# schematic-oshtest.net
KiCad netlist of a schematic drawn in EAGLE
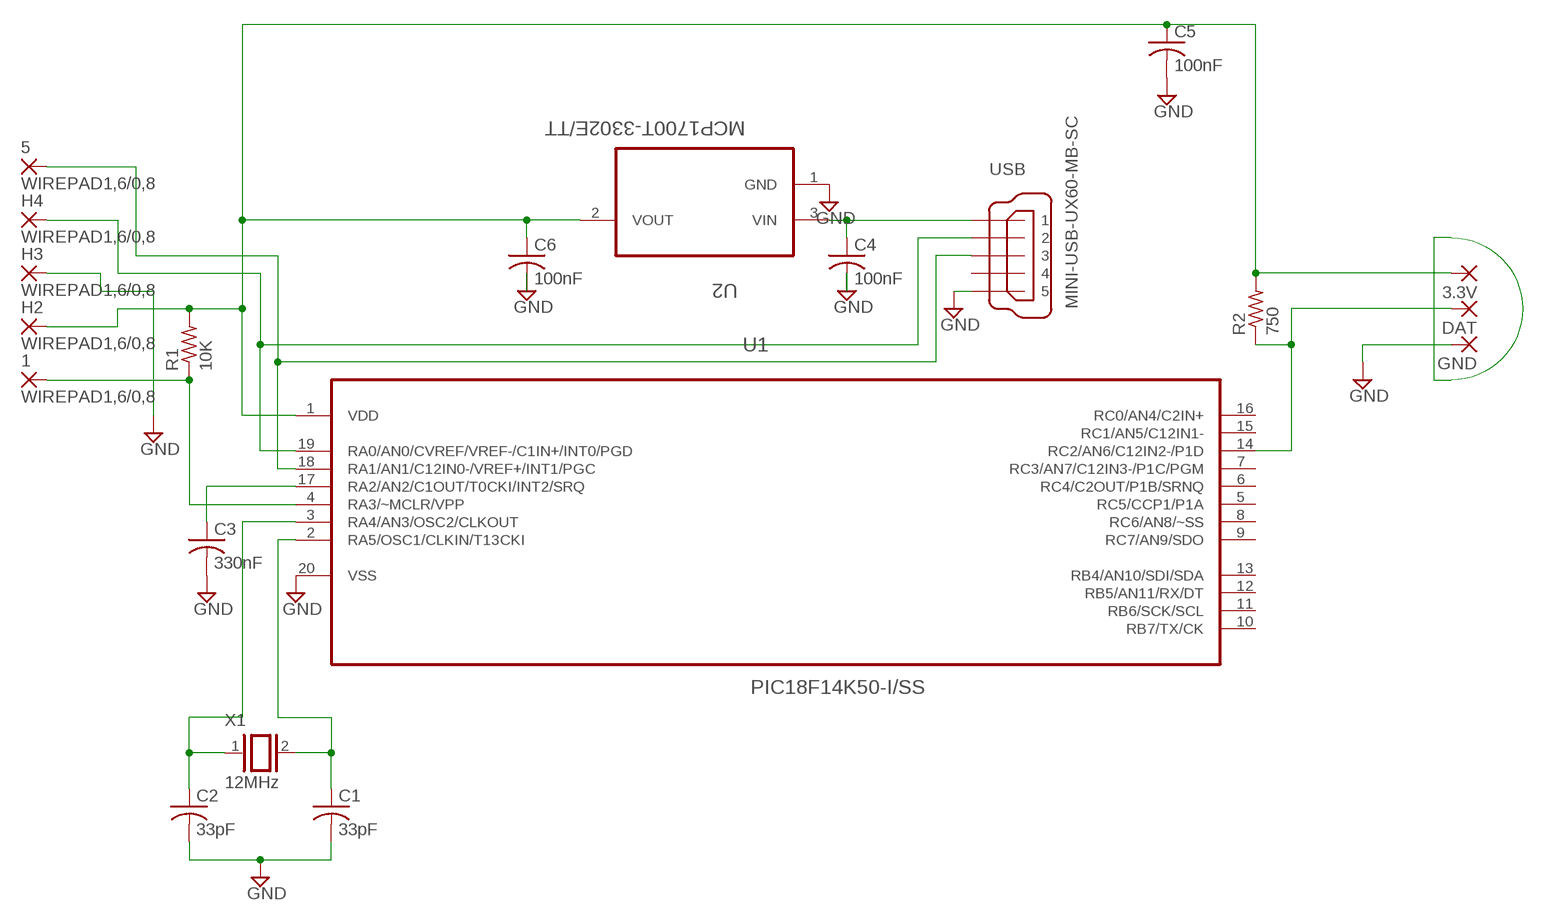
[diagram p0: schematic, sheet 1]

(export (version "E")
  (design (tool "Eeschema 10.0.6"))
  (components
    (comp (ref "1")
      (value "WIREPAD1,6/0,8")
      (footprint "eagle-import:1,6_0,8")
      (libsource (lib "eagle-import") (part "WIREPAD1,6/0,8"))
    )
    (comp (ref "3.3V")
      (value "SMD2")
      (footprint "eagle-import:SMD1,27-2,54")
      (libsource (lib "eagle-import") (part "SMD2"))
    )
    (comp (ref "5")
      (value "WIREPAD1,6/0,8")
      (footprint "eagle-import:1,6_0,8")
      (libsource (lib "eagle-import") (part "WIREPAD1,6/0,8"))
    )
    (comp (ref "C1")
      (value "33pF")
      (footprint "eagle-import:C0402")
      (libsource (lib "eagle-import") (part "C-USC0402"))
    )
    (comp (ref "C2")
      (value "33pF")
      (footprint "eagle-import:C0402")
      (libsource (lib "eagle-import") (part "C-USC0402"))
    )
    (comp (ref "C3")
      (value "330nF")
      (footprint "eagle-import:C0603")
      (libsource (lib "eagle-import") (part "C-USC0603"))
    )
    (comp (ref "C4")
      (value "100nF")
      (footprint "eagle-import:C0402")
      (libsource (lib "eagle-import") (part "C-USC0402"))
    )
    (comp (ref "C5")
      (value "100nF")
      (footprint "eagle-import:C0402")
      (libsource (lib "eagle-import") (part "C-USC0402"))
    )
    (comp (ref "C6")
      (value "100nF")
      (footprint "eagle-import:C0402")
      (libsource (lib "eagle-import") (part "C-USC0402"))
    )
    (comp (ref "DAT")
      (value "SMD2")
      (footprint "eagle-import:SMD1,27-2,54")
      (libsource (lib "eagle-import") (part "SMD2"))
    )
    (comp (ref "GND")
      (value "SMD2")
      (footprint "eagle-import:SMD1,27-2,54")
      (libsource (lib "eagle-import") (part "SMD2"))
    )
    (comp (ref "H2")
      (value "WIREPAD1,6/0,8")
      (footprint "eagle-import:1,6_0,8")
      (libsource (lib "eagle-import") (part "WIREPAD1,6/0,8"))
    )
    (comp (ref "H3")
      (value "WIREPAD1,6/0,8")
      (footprint "eagle-import:1,6_0,8")
      (libsource (lib "eagle-import") (part "WIREPAD1,6/0,8"))
    )
    (comp (ref "H4")
      (value "WIREPAD1,6/0,8")
      (footprint "eagle-import:1,6_0,8")
      (libsource (lib "eagle-import") (part "WIREPAD1,6/0,8"))
    )
    (comp (ref "R1")
      (value "10K")
      (footprint "eagle-import:R0805")
      (libsource (lib "eagle-import") (part "R-US_R0805"))
    )
    (comp (ref "R2")
      (value "750")
      (footprint "eagle-import:R0805")
      (libsource (lib "eagle-import") (part "R-US_R0805"))
    )
    (comp (ref "U1")
      (value "PIC18F14K50-I/SS")
      (footprint "eagle-import:SOP65P780X200-20N")
      (libsource (lib "eagle-import") (part "PIC18F14K50-I/SS"))
    )
    (comp (ref "U2")
      (value "MCP1700T-3302E/TT")
      (footprint "eagle-import:SOT95P237X112-3N")
      (libsource (lib "eagle-import") (part "MCP1700T-3302E/TT"))
    )
    (comp (ref "USB")
      (value "MINI-USB-UX60-MB-SC")
      (footprint "eagle-import:UX60-MB-SC")
      (libsource (lib "eagle-import") (part "MINI-USB-UX60-MB-SC"))
    )
    (comp (ref "X1")
      (value "12MHz")
      (footprint "eagle-import:QS")
      (libsource (lib "eagle-import") (part "XTAL/S"))
    )
  )
  (nets
    (net (code "1") (name "GND") (class "Default")
      (node (ref "C1") (pin "2") (pinfunction "2_2") (pintype "passive"))
      (node (ref "C2") (pin "2") (pinfunction "2_2") (pintype "passive"))
      (node (ref "C3") (pin "2") (pinfunction "2_2") (pintype "passive"))
      (node (ref "C4") (pin "2") (pinfunction "2_2") (pintype "passive"))
      (node (ref "C5") (pin "2") (pinfunction "2_2") (pintype "passive"))
      (node (ref "C6") (pin "2") (pinfunction "2_2") (pintype "passive"))
      (node (ref "GND") (pin "1") (pinfunction "P_1") (pintype "passive"))
      (node (ref "H3") (pin "1") (pinfunction "P_1") (pintype "passive"))
      (node (ref "U1") (pin "20") (pinfunction "VSS_20") (pintype "power_in"))
      (node (ref "U2") (pin "1") (pinfunction "GND_1") (pintype "passive"))
      (node (ref "USB") (pin "P$5") (pinfunction "5_P$5") (pintype "input"))
    )
    (net (code "2") (name "Net-(1-P)") (class "Default")
      (node (ref "1") (pin "1") (pinfunction "P_1") (pintype "passive"))
      (node (ref "R1") (pin "1") (pinfunction "1_1") (pintype "passive"))
      (node (ref "U1") (pin "4") (pinfunction "RA3/~{MCLR/VPP}_4") (pintype "input"))
    )
    (net (code "3") (name "Net-(3.3V-P)") (class "Default")
      (node (ref "3.3V") (pin "1") (pinfunction "P_1") (pintype "passive"))
      (node (ref "C5") (pin "1") (pinfunction "1_1") (pintype "passive"))
      (node (ref "C6") (pin "1") (pinfunction "1_1") (pintype "passive"))
      (node (ref "H2") (pin "1") (pinfunction "P_1") (pintype "passive"))
      (node (ref "R1") (pin "2") (pinfunction "2_2") (pintype "passive"))
      (node (ref "R2") (pin "2") (pinfunction "2_2") (pintype "passive"))
      (node (ref "U1") (pin "1") (pinfunction "VDD_1") (pintype "power_in"))
      (node (ref "U2") (pin "2") (pinfunction "VOUT_2") (pintype "output"))
    )
    (net (code "4") (name "Net-(5-P)") (class "Default")
      (node (ref "5") (pin "1") (pinfunction "P_1") (pintype "passive"))
      (node (ref "U1") (pin "18") (pinfunction "RA1/AN1/C12IN0-/VREF+/INT1/PGC_18") (pintype "bidirectional"))
      (node (ref "USB") (pin "P$3") (pinfunction "3_P$3") (pintype "input"))
    )
    (net (code "5") (name "Net-(DAT-P)") (class "Default")
      (node (ref "DAT") (pin "1") (pinfunction "P_1") (pintype "passive"))
      (node (ref "R2") (pin "1") (pinfunction "1_1") (pintype "passive"))
      (node (ref "U1") (pin "14") (pinfunction "RC2/AN6/C12IN2-/P1D_14") (pintype "bidirectional"))
    )
    (net (code "6") (name "Net-(H4-P)") (class "Default")
      (node (ref "H4") (pin "1") (pinfunction "P_1") (pintype "passive"))
      (node (ref "U1") (pin "19") (pinfunction "RA0/AN0/CVREF/VREF-/C1IN+/INT0/PGD_19") (pintype "bidirectional"))
      (node (ref "USB") (pin "P$2") (pinfunction "2_P$2") (pintype "input"))
    )
    (net (code "7") (name "Net-(U1-RA2{slash}AN2{slash}C1OUT{slash}T0CKI{slash}INT2{slash}SRQ)") (class "Default")
      (node (ref "C3") (pin "1") (pinfunction "1_1") (pintype "passive"))
      (node (ref "U1") (pin "17") (pinfunction "RA2/AN2/C1OUT/T0CKI/INT2/SRQ_17") (pintype "input"))
    )
    (net (code "8") (name "Net-(U1-RA4{slash}AN3{slash}OSC2{slash}CLKOUT)") (class "Default")
      (node (ref "C2") (pin "1") (pinfunction "1_1") (pintype "passive"))
      (node (ref "U1") (pin "3") (pinfunction "RA4/AN3/OSC2/CLKOUT_3") (pintype "bidirectional"))
      (node (ref "X1") (pin "1") (pinfunction "1_1") (pintype "passive"))
    )
    (net (code "9") (name "Net-(U1-RA5{slash}OSC1{slash}CLKIN{slash}T13CKI)") (class "Default")
      (node (ref "C1") (pin "1") (pinfunction "1_1") (pintype "passive"))
      (node (ref "U1") (pin "2") (pinfunction "RA5/OSC1/CLKIN/T13CKI_2") (pintype "bidirectional"))
      (node (ref "X1") (pin "2") (pinfunction "2_2") (pintype "passive"))
    )
    (net (code "10") (name "Net-(U2-VIN)") (class "Default")
      (node (ref "C4") (pin "1") (pinfunction "1_1") (pintype "passive"))
      (node (ref "U2") (pin "3") (pinfunction "VIN_3") (pintype "input"))
      (node (ref "USB") (pin "P$1") (pinfunction "1_P$1") (pintype "input"))
    )
    (net (code "11") (name "unconnected-(U1-RB4{slash}AN10{slash}SDI{slash}SDA-Pad13)") (class "Default")
      (node (ref "U1") (pin "13") (pinfunction "RB4/AN10/SDI/SDA_13") (pintype "bidirectional"))
    )
    (net (code "12") (name "unconnected-(U1-RB5{slash}AN11{slash}RX{slash}DT-Pad12)") (class "Default")
      (node (ref "U1") (pin "12") (pinfunction "RB5/AN11/RX/DT_12") (pintype "bidirectional"))
    )
    (net (code "13") (name "unconnected-(U1-RB6{slash}SCK{slash}SCL-Pad11)") (class "Default")
      (node (ref "U1") (pin "11") (pinfunction "RB6/SCK/SCL_11") (pintype "bidirectional"))
    )
    (net (code "14") (name "unconnected-(U1-RB7{slash}TX{slash}CK-Pad10)") (class "Default")
      (node (ref "U1") (pin "10") (pinfunction "RB7/TX/CK_10") (pintype "bidirectional"))
    )
    (net (code "15") (name "unconnected-(U1-RC0{slash}AN4{slash}C2IN+-Pad16)") (class "Default")
      (node (ref "U1") (pin "16") (pinfunction "RC0/AN4/C2IN+_16") (pintype "bidirectional"))
    )
    (net (code "16") (name "unconnected-(U1-RC1{slash}AN5{slash}C12IN1--Pad15)") (class "Default")
      (node (ref "U1") (pin "15") (pinfunction "RC1/AN5/C12IN1-_15") (pintype "bidirectional"))
    )
    (net (code "17") (name "unconnected-(U1-RC3{slash}AN7{slash}C12IN3-{slash}P1C{slash}PGM-Pad7)") (class "Default")
      (node (ref "U1") (pin "7") (pinfunction "RC3/AN7/C12IN3-/P1C/PGM_7") (pintype "bidirectional"))
    )
    (net (code "18") (name "unconnected-(U1-RC4{slash}C2OUT{slash}P1B{slash}SRNQ-Pad6)") (class "Default")
      (node (ref "U1") (pin "6") (pinfunction "RC4/C2OUT/P1B/SRNQ_6") (pintype "bidirectional"))
    )
    (net (code "19") (name "unconnected-(U1-RC5{slash}CCP1{slash}P1A-Pad5)") (class "Default")
      (node (ref "U1") (pin "5") (pinfunction "RC5/CCP1/P1A_5") (pintype "bidirectional"))
    )
    (net (code "20") (name "unconnected-(U1-RC6{slash}AN8{slash}~{SS}-Pad8)") (class "Default")
      (node (ref "U1") (pin "8") (pinfunction "RC6/AN8/~{SS}_8") (pintype "bidirectional"))
    )
    (net (code "21") (name "unconnected-(U1-RC7{slash}AN9{slash}SDO-Pad9)") (class "Default")
      (node (ref "U1") (pin "9") (pinfunction "RC7/AN9/SDO_9") (pintype "bidirectional"))
    )
    (net (code "22") (name "unconnected-(USB-4-PadP$4)") (class "Default")
      (node (ref "USB") (pin "P$4") (pinfunction "4_P$4") (pintype "input"))
    )
  )
)
